# test.net
KiCad netlist of a schematic drawn in EAGLE
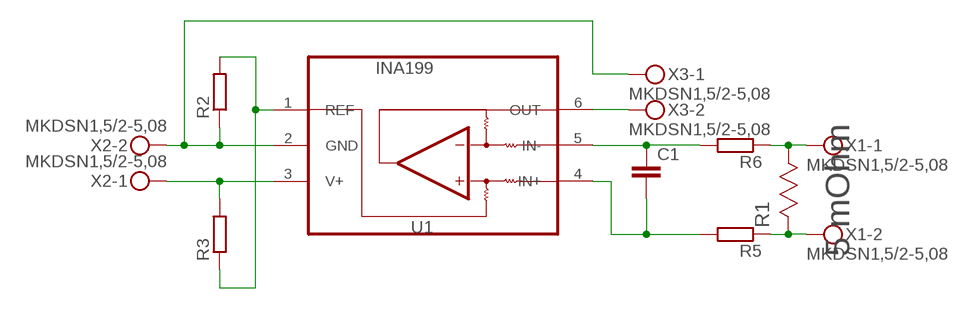
[diagram p0: schematic, sheet 1]

(export (version "E")
  (design (tool "Eeschema 10.0.6"))
  (components
    (comp (ref "C1")
      (value "C-EUC0805")
      (footprint "eagle-import:C0805")
      (libsource (lib "eagle-import") (part "C-EUC0805"))
    )
    (comp (ref "R1")
      (value "5 mOhm")
      (footprint "eagle-import:RESC6332X110N")
      (fields (field (name "MPN") "ERJ-M1WSF5M0U") (field (name "TOLERANCE") "±1%"))
      (libsource (lib "eagle-import") (part "ERJ-M1WSF5M0U"))
    )
    (comp (ref "R2")
      (value "R-EU_R0805")
      (footprint "eagle-import:R0805")
      (libsource (lib "eagle-import") (part "R-EU_R0805"))
    )
    (comp (ref "R3")
      (value "R-EU_R0805")
      (footprint "eagle-import:R0805")
      (libsource (lib "eagle-import") (part "R-EU_R0805"))
    )
    (comp (ref "R5")
      (value "R-EU_R0805")
      (footprint "eagle-import:R0805")
      (libsource (lib "eagle-import") (part "R-EU_R0805"))
    )
    (comp (ref "R6")
      (value "R-EU_R0805")
      (footprint "eagle-import:R0805")
      (libsource (lib "eagle-import") (part "R-EU_R0805"))
    )
    (comp (ref "U1")
      (value "INA199")
      (footprint "eagle-import:SC70-6L")
      (libsource (lib "eagle-import") (part "INA199"))
    )
    (comp (ref "X1")
      (value "MKDSN1,5/2-5,08")
      (footprint "eagle-import:MKDSN1,5_2-5,08")
      (fields (field (name "MPN") "MKDSN 1,5/2-5.08"))
      (libsource (lib "eagle-import") (part "MKDSN1,5/2-5,08"))
    )
    (comp (ref "X2")
      (value "MKDSN1,5/2-5,08")
      (footprint "eagle-import:MKDSN1,5_2-5,08")
      (fields (field (name "MPN") "MKDSN 1,5/2-5.08"))
      (libsource (lib "eagle-import") (part "MKDSN1,5/2-5,08"))
    )
    (comp (ref "X3")
      (value "MKDSN1,5/2-5,08")
      (footprint "eagle-import:MKDSN1,5_2-5,08")
      (fields (field (name "MPN") "MKDSN 1,5/2-5.08"))
      (libsource (lib "eagle-import") (part "MKDSN1,5/2-5,08"))
    )
  )
  (nets
    (net (code "1") (name "Net-(R1-R1)") (class "Default")
      (node (ref "R1") (pin "1") (pinfunction "R1_1") (pintype "passive"))
      (node (ref "R6") (pin "1") (pinfunction "1_1") (pintype "passive"))
      (node (ref "X1") (pin "1") (pinfunction "KL_1") (pintype "passive"))
    )
    (net (code "2") (name "Net-(R1-R2)") (class "Default")
      (node (ref "R1") (pin "2") (pinfunction "R2_2") (pintype "passive"))
      (node (ref "R5") (pin "1") (pinfunction "1_1") (pintype "passive"))
      (node (ref "X1") (pin "2") (pinfunction "KL_2") (pintype "passive"))
    )
    (net (code "3") (name "Net-(U1-GND)") (class "Default")
      (node (ref "R2") (pin "1") (pinfunction "1_1") (pintype "passive"))
      (node (ref "U1") (pin "2") (pinfunction "GND_2") (pintype "power_in"))
      (node (ref "X2") (pin "2") (pinfunction "KL_2") (pintype "passive"))
      (node (ref "X3") (pin "1") (pinfunction "KL_1") (pintype "passive"))
    )
    (net (code "4") (name "Net-(U1-IN+)") (class "Default")
      (node (ref "C1") (pin "2") (pinfunction "2_2") (pintype "passive"))
      (node (ref "R5") (pin "2") (pinfunction "2_2") (pintype "passive"))
      (node (ref "U1") (pin "4") (pinfunction "IN+_4") (pintype "input"))
    )
    (net (code "5") (name "Net-(U1-IN-)") (class "Default")
      (node (ref "C1") (pin "1") (pinfunction "1_1") (pintype "passive"))
      (node (ref "R6") (pin "2") (pinfunction "2_2") (pintype "passive"))
      (node (ref "U1") (pin "5") (pinfunction "IN-_5") (pintype "input"))
    )
    (net (code "6") (name "Net-(U1-OUT)") (class "Default")
      (node (ref "U1") (pin "6") (pinfunction "OUT_6") (pintype "bidirectional"))
      (node (ref "X3") (pin "2") (pinfunction "KL_2") (pintype "passive"))
    )
    (net (code "7") (name "Net-(U1-REF)") (class "Default")
      (node (ref "R2") (pin "2") (pinfunction "2_2") (pintype "passive"))
      (node (ref "R3") (pin "1") (pinfunction "1_1") (pintype "passive"))
      (node (ref "U1") (pin "1") (pinfunction "REF_1") (pintype "input"))
    )
    (net (code "8") (name "Net-(U1-V+)") (class "Default")
      (node (ref "R3") (pin "2") (pinfunction "2_2") (pintype "passive"))
      (node (ref "U1") (pin "3") (pinfunction "V+_3") (pintype "power_in"))
      (node (ref "X2") (pin "1") (pinfunction "KL_1") (pintype "passive"))
    )
  )
)
